# radio_expansion.net
KiCad netlist of a schematic drawn in EAGLE
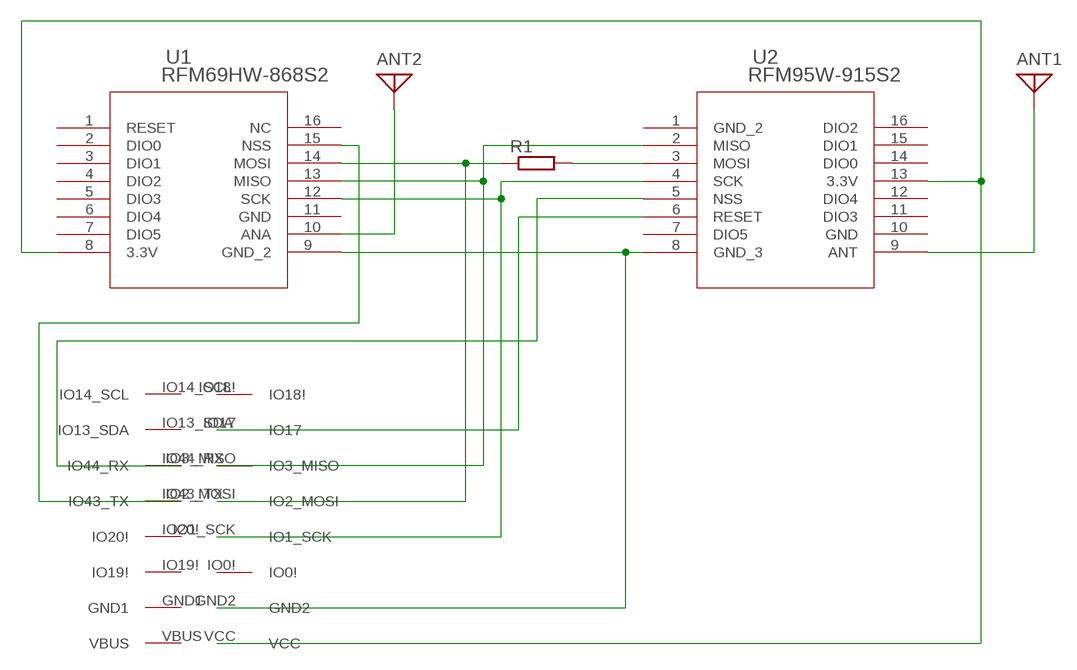
[diagram p0: schematic, sheet 1]

(export (version "E")
  (design (tool "Eeschema 10.0.6"))
  (components
    (comp (ref "ANT1")
      (value "ANTENNA")
      (footprint "eagle-import:PAD-01")
      (libsource (lib "eagle-import") (part "ANTENNA"))
    )
    (comp (ref "ANT2")
      (value "ANTENNA")
      (footprint "eagle-import:PAD-01")
      (libsource (lib "eagle-import") (part "ANTENNA"))
    )
    (comp (ref "R1")
      (value "R-EU_M5923")
      (footprint "eagle-import:M5923")
      (libsource (lib "eagle-import") (part "R-EU_M5923"))
    )
    (comp (ref "U$1")
      (value "SOLARTERM_EXP")
      (footprint "eagle-import:CONN")
      (libsource (lib "eagle-import") (part "SOLARTERM_EXP"))
    )
    (comp (ref "U1")
      (value "RFM69HW-868S2")
      (footprint "eagle-import:RFM69HW_S2_HRF")
      (fields (field (name "COPYRIGHT") "Copyright (C) 2026 Ultra Librarian. All rights reserved."))
      (libsource (lib "eagle-import") (part "RFM69HW-868S2"))
    )
    (comp (ref "U2")
      (value "RFM95W-915S2")
      (footprint "eagle-import:IC16_RFM95W-915S2_RFS")
      (fields (field (name "COPYRIGHT") "Copyright (C) 2026 Ultra Librarian. All rights reserved."))
      (libsource (lib "eagle-import") (part "RFM95W-915S2"))
    )
  )
  (nets
    (net (code "1") (name "/MOSI") (class "Default")
      (node (ref "R1") (pin "1") (pinfunction "1_1") (pintype "passive"))
      (node (ref "R1") (pin "2") (pinfunction "2_2") (pintype "passive"))
      (node (ref "U$1") (pin "IO2_MOSI") (pinfunction "IO2_MOSI_IO2_MOSI") (pintype "bidirectional"))
      (node (ref "U1") (pin "14") (pinfunction "MOSI_14") (pintype "input"))
      (node (ref "U2") (pin "3") (pinfunction "MOSI_3") (pintype "passive"))
    )
    (net (code "2") (name "Net-(U1-3.3V)") (class "Default")
      (node (ref "U$1") (pin "VCC") (pinfunction "VCC_VCC") (pintype "bidirectional"))
      (node (ref "U1") (pin "8") (pinfunction "3.3V_8") (pintype "power_in"))
      (node (ref "U2") (pin "13") (pinfunction "3.3V_13") (pintype "passive"))
    )
    (net (code "3") (name "Net-(U1-ANA)") (class "Default")
      (node (ref "ANT2") (pin "1") (pinfunction "1_1") (pintype "output"))
      (node (ref "U1") (pin "10") (pinfunction "ANA_10") (pintype "passive"))
    )
    (net (code "4") (name "Net-(U1-GND_2)") (class "Default")
      (node (ref "U$1") (pin "GND2") (pinfunction "GND2_GND2") (pintype "bidirectional"))
      (node (ref "U1") (pin "9") (pinfunction "GND_2_9") (pintype "passive"))
      (node (ref "U2") (pin "8") (pinfunction "GND_3_8") (pintype "passive"))
    )
    (net (code "5") (name "Net-(U1-MISO)") (class "Default")
      (node (ref "U$1") (pin "IO3_MISO") (pinfunction "IO3_MISO_IO3_MISO") (pintype "bidirectional"))
      (node (ref "U1") (pin "13") (pinfunction "MISO_13") (pintype "output"))
      (node (ref "U2") (pin "2") (pinfunction "MISO_2") (pintype "passive"))
    )
    (net (code "6") (name "Net-(U1-NSS)") (class "Default")
      (node (ref "U$1") (pin "IO43_TX") (pinfunction "IO43_TX_IO43_TX") (pintype "bidirectional"))
      (node (ref "U1") (pin "15") (pinfunction "NSS_15") (pintype "input"))
    )
    (net (code "7") (name "Net-(U1-SCK)") (class "Default")
      (node (ref "U$1") (pin "IO1_SCK") (pinfunction "IO1_SCK_IO1_SCK") (pintype "bidirectional"))
      (node (ref "U1") (pin "12") (pinfunction "SCK_12") (pintype "input"))
      (node (ref "U2") (pin "4") (pinfunction "SCK_4") (pintype "passive"))
    )
    (net (code "8") (name "Net-(U2-ANT)") (class "Default")
      (node (ref "ANT1") (pin "1") (pinfunction "1_1") (pintype "output"))
      (node (ref "U2") (pin "9") (pinfunction "ANT_9") (pintype "passive"))
    )
    (net (code "9") (name "Net-(U2-NSS)") (class "Default")
      (node (ref "U$1") (pin "IO44_RX") (pinfunction "IO44_RX_IO44_RX") (pintype "bidirectional"))
      (node (ref "U2") (pin "5") (pinfunction "NSS_5") (pintype "passive"))
    )
    (net (code "10") (name "Net-(U2-RESET)") (class "Default")
      (node (ref "U$1") (pin "IO17") (pinfunction "IO17_IO17") (pintype "bidirectional"))
      (node (ref "U2") (pin "6") (pinfunction "RESET_6") (pintype "passive"))
    )
    (net (code "11") (name "unconnected-(U$1-IO0~{}-PadIO0!)") (class "Default")
      (node (ref "U$1") (pin "IO0!") (pinfunction "IO0~{}_IO0!") (pintype "bidirectional"))
    )
    (net (code "12") (name "unconnected-(U$1-IO18~{}-PadIO18!)") (class "Default")
      (node (ref "U$1") (pin "IO18!") (pinfunction "IO18~{}_IO18!") (pintype "bidirectional"))
    )
    (net (code "13") (name "unconnected-(U$1-IO19~{}-PadIO19!)") (class "Default")
      (node (ref "U$1") (pin "IO19!") (pinfunction "IO19~{}_IO19!") (pintype "bidirectional"))
    )
    (net (code "14") (name "unconnected-(U$1-IO20~{}-PadIO20!)") (class "Default")
      (node (ref "U$1") (pin "IO20!") (pinfunction "IO20~{}_IO20!") (pintype "bidirectional"))
    )
    (net (code "15") (name "unconnected-(U$1-PadGND1)") (class "Default")
      (node (ref "U$1") (pin "GND1") (pinfunction "GND1_GND1") (pintype "bidirectional"))
    )
    (net (code "16") (name "unconnected-(U$1-PadIO13_SDA)") (class "Default")
      (node (ref "U$1") (pin "IO13_SDA") (pinfunction "IO13_SDA_IO13_SDA") (pintype "bidirectional"))
    )
    (net (code "17") (name "unconnected-(U$1-PadIO14_SCL)") (class "Default")
      (node (ref "U$1") (pin "IO14_SCL") (pinfunction "IO14_SCL_IO14_SCL") (pintype "bidirectional"))
    )
    (net (code "18") (name "unconnected-(U$1-PadVBUS)") (class "Default")
      (node (ref "U$1") (pin "VBUS") (pinfunction "VBUS_VBUS") (pintype "bidirectional"))
    )
    (net (code "19") (name "unconnected-(U1-DIO0-Pad2)") (class "Default")
      (node (ref "U1") (pin "2") (pinfunction "DIO0_2") (pintype "bidirectional"))
    )
    (net (code "20") (name "unconnected-(U1-DIO1-Pad3)") (class "Default")
      (node (ref "U1") (pin "3") (pinfunction "DIO1_3") (pintype "bidirectional"))
    )
    (net (code "21") (name "unconnected-(U1-DIO2-Pad4)") (class "Default")
      (node (ref "U1") (pin "4") (pinfunction "DIO2_4") (pintype "bidirectional"))
    )
    (net (code "22") (name "unconnected-(U1-DIO3-Pad5)") (class "Default")
      (node (ref "U1") (pin "5") (pinfunction "DIO3_5") (pintype "bidirectional"))
    )
    (net (code "23") (name "unconnected-(U1-DIO4-Pad6)") (class "Default")
      (node (ref "U1") (pin "6") (pinfunction "DIO4_6") (pintype "bidirectional"))
    )
    (net (code "24") (name "unconnected-(U1-DIO5-Pad7)") (class "Default")
      (node (ref "U1") (pin "7") (pinfunction "DIO5_7") (pintype "bidirectional"))
    )
    (net (code "25") (name "unconnected-(U1-GND-Pad11)") (class "Default")
      (node (ref "U1") (pin "11") (pinfunction "GND_11") (pintype "passive"))
    )
    (net (code "26") (name "unconnected-(U1-NC-Pad16)") (class "Default")
      (node (ref "U1") (pin "16") (pinfunction "NC_16") (pintype "no_connect"))
    )
    (net (code "27") (name "unconnected-(U1-RESET-Pad1)") (class "Default")
      (node (ref "U1") (pin "1") (pinfunction "RESET_1") (pintype "bidirectional"))
    )
    (net (code "28") (name "unconnected-(U2-DIO0-Pad14)") (class "Default")
      (node (ref "U2") (pin "14") (pinfunction "DIO0_14") (pintype "bidirectional"))
    )
    (net (code "29") (name "unconnected-(U2-DIO1-Pad15)") (class "Default")
      (node (ref "U2") (pin "15") (pinfunction "DIO1_15") (pintype "bidirectional"))
    )
    (net (code "30") (name "unconnected-(U2-DIO2-Pad16)") (class "Default")
      (node (ref "U2") (pin "16") (pinfunction "DIO2_16") (pintype "bidirectional"))
    )
    (net (code "31") (name "unconnected-(U2-DIO3-Pad11)") (class "Default")
      (node (ref "U2") (pin "11") (pinfunction "DIO3_11") (pintype "bidirectional"))
    )
    (net (code "32") (name "unconnected-(U2-DIO4-Pad12)") (class "Default")
      (node (ref "U2") (pin "12") (pinfunction "DIO4_12") (pintype "bidirectional"))
    )
    (net (code "33") (name "unconnected-(U2-DIO5-Pad7)") (class "Default")
      (node (ref "U2") (pin "7") (pinfunction "DIO5_7") (pintype "bidirectional"))
    )
    (net (code "34") (name "unconnected-(U2-GND-Pad10)") (class "Default")
      (node (ref "U2") (pin "10") (pinfunction "GND_10") (pintype "passive"))
    )
    (net (code "35") (name "unconnected-(U2-GND_2-Pad1)") (class "Default")
      (node (ref "U2") (pin "1") (pinfunction "GND_2_1") (pintype "passive"))
    )
  )
)
